# jlink_to_tag.net
KiCad netlist of a schematic drawn in EAGLE
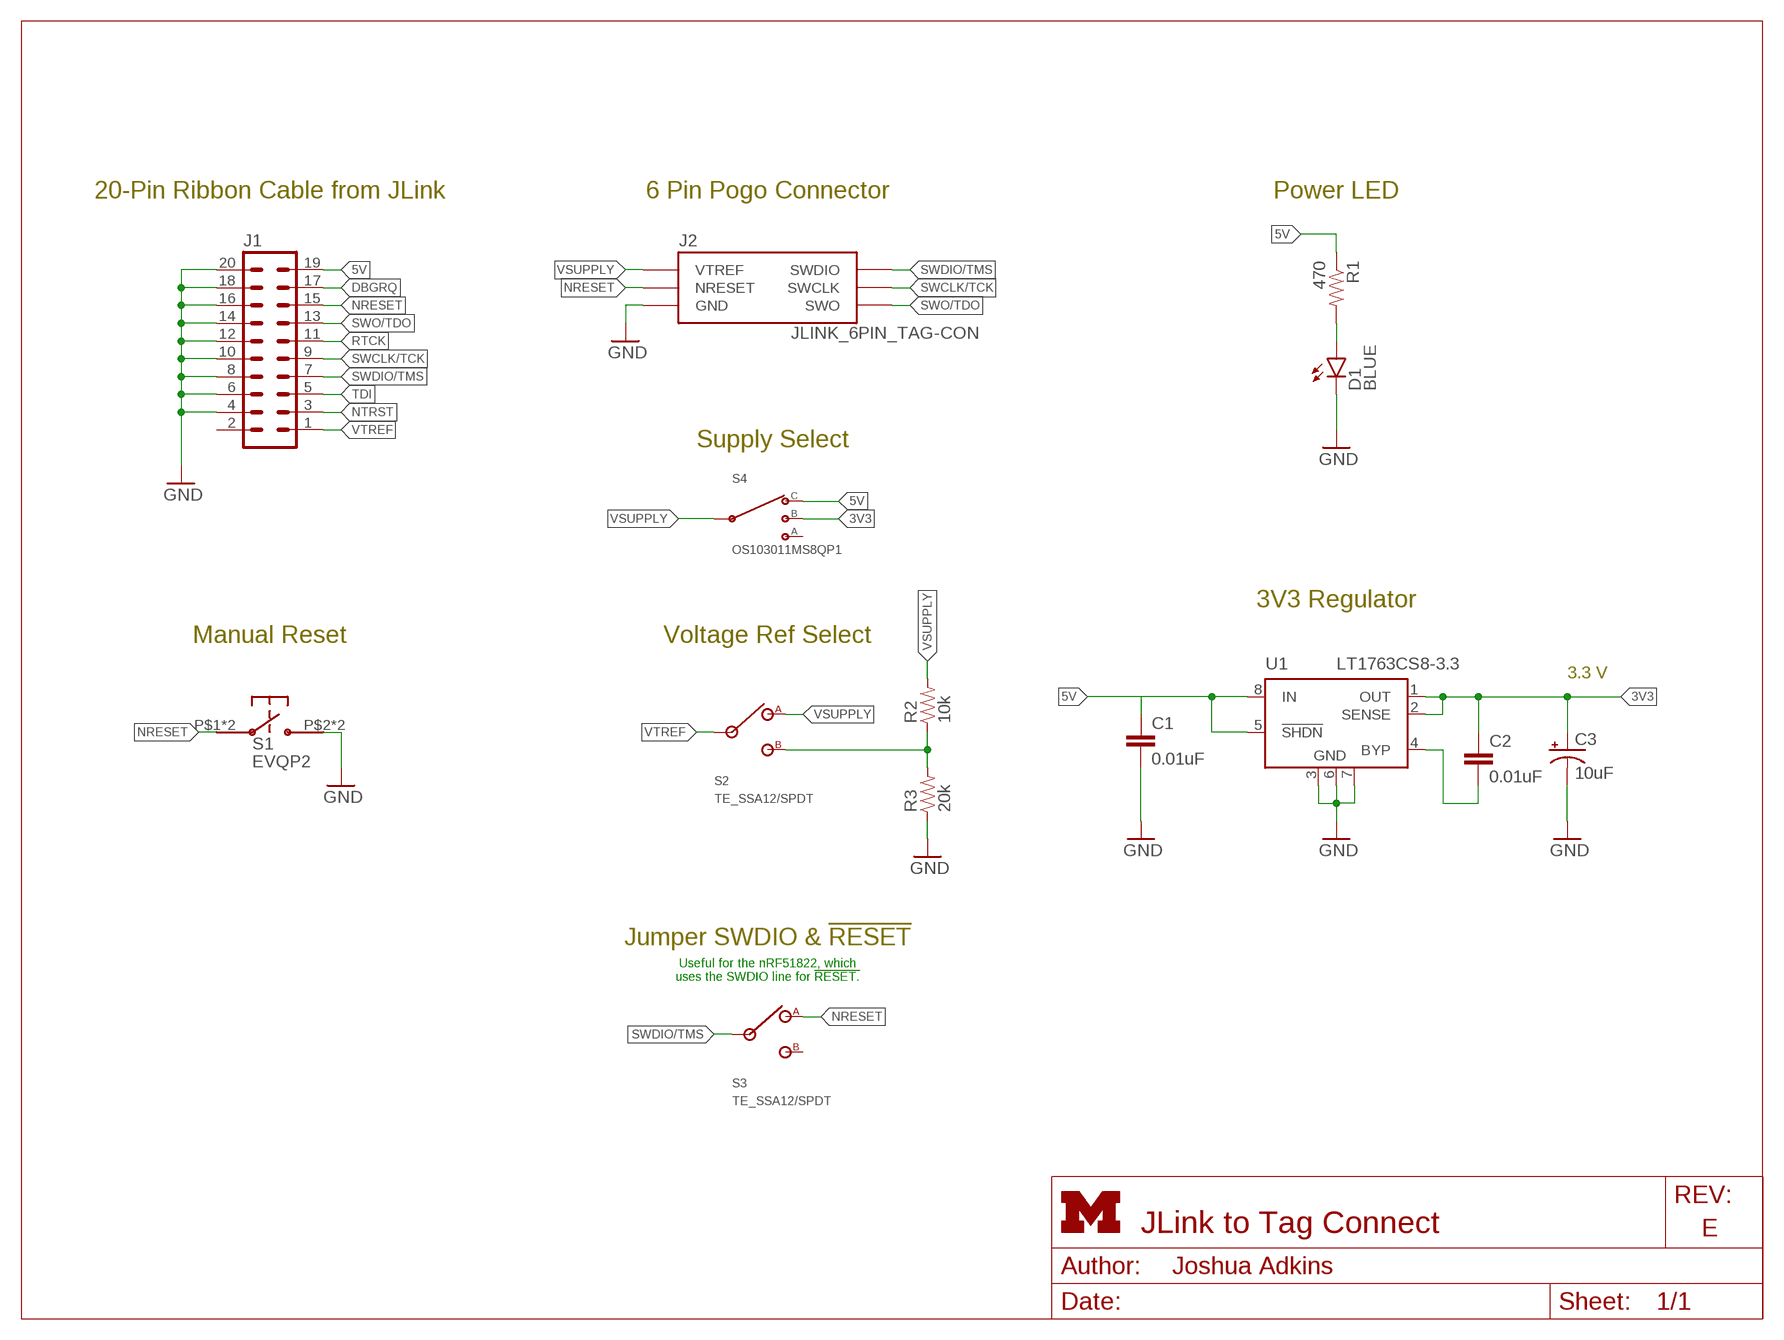
[diagram p0: schematic, sheet 1]

(export (version "E")
  (design (tool "Eeschema 10.0.6"))
  (components
    (comp (ref "C1")
      (value "0.01uF")
      (footprint "eagle-import:C0603")
      (libsource (lib "eagle-import") (part "C-EUC0603"))
    )
    (comp (ref "C2")
      (value "0.01uF")
      (footprint "eagle-import:C0603")
      (libsource (lib "eagle-import") (part "C-EUC0603"))
    )
    (comp (ref "C3")
      (value "10uF")
      (footprint "eagle-import:EIA3216")
      (libsource (lib "eagle-import") (part "CAP_POL1206"))
    )
    (comp (ref "D1")
      (value "BLUE")
      (footprint "eagle-import:LED-0603")
      (libsource (lib "eagle-import") (part "LED-BLUE0603"))
    )
    (comp (ref "J1")
      (value "ML20")
      (footprint "eagle-import:ML20")
      (libsource (lib "eagle-import") (part "ML20"))
    )
    (comp (ref "J2")
      (value "JLINK_6PIN_TAG-CON")
      (footprint "eagle-import:2X3_MALE_SHROUDED_0.100")
      (libsource (lib "eagle-import") (part "JLINK_6PIN_TAG-CON"))
    )
    (comp (ref "R1")
      (value "470")
      (footprint "eagle-import:0603-RES")
      (libsource (lib "eagle-import") (part "RESISTOR0603-RES"))
    )
    (comp (ref "R2")
      (value "10k")
      (footprint "eagle-import:0603-RES")
      (libsource (lib "eagle-import") (part "RESISTOR0603_RES"))
    )
    (comp (ref "R3")
      (value "20k")
      (footprint "eagle-import:0603-RES")
      (libsource (lib "eagle-import") (part "RESISTOR0603_RES"))
    )
    (comp (ref "S1")
      (value "EVQP2")
      (footprint "eagle-import:EVQP2")
      (libsource (lib "eagle-import") (part "EVQP2"))
    )
    (comp (ref "S2")
      (value "TE_SSA12/SPDT")
      (footprint "eagle-import:TE_SSA12_SPDT")
      (fields (field (name "DIGIKEY") "2223-SLW-883935-2A-D-ND") (field (name "MPN") "SLW-883935-2A-D"))
      (libsource (lib "eagle-import") (part "TE_SSA12/SPDT"))
    )
    (comp (ref "S3")
      (value "TE_SSA12/SPDT")
      (footprint "eagle-import:TE_SSA12_SPDT")
      (fields (field (name "DIGIKEY") "2223-SLW-883935-2A-D-ND") (field (name "MPN") "SLW-883935-2A-D"))
      (libsource (lib "eagle-import") (part "TE_SSA12/SPDT"))
    )
    (comp (ref "S4")
      (value "OS103011MS8QP1")
      (footprint "eagle-import:OS102011MS8QP1")
      (libsource (lib "eagle-import") (part "OS103011MS8QP1"))
    )
    (comp (ref "U1")
      (value "LT1763CS8-3.3")
      (footprint "eagle-import:SOIC8")
      (libsource (lib "eagle-import") (part "LT1763CS8-3.3"))
    )
  )
  (nets
    (net (code "1") (name "3V3") (class "Default")
      (node (ref "C2") (pin "1") (pinfunction "1_1") (pintype "passive"))
      (node (ref "C3") (pin "A") (pinfunction "+_A") (pintype "passive"))
      (node (ref "S4") (pin "3") (pinfunction "2_3") (pintype "bidirectional"))
      (node (ref "U1") (pin "1") (pinfunction "OUT_1") (pintype "passive"))
      (node (ref "U1") (pin "2") (pinfunction "SENSE_2") (pintype "input"))
    )
    (net (code "2") (name "5V") (class "Default")
      (node (ref "C1") (pin "1") (pinfunction "1_1") (pintype "passive"))
      (node (ref "J1") (pin "19") (pinfunction "19_19") (pintype "passive"))
      (node (ref "R1") (pin "1") (pinfunction "1_1") (pintype "passive"))
      (node (ref "S4") (pin "4") (pinfunction "3_4") (pintype "bidirectional"))
      (node (ref "U1") (pin "5") (pinfunction "~{SHDN}_5") (pintype "input"))
      (node (ref "U1") (pin "8") (pinfunction "IN_8") (pintype "input"))
    )
    (net (code "3") (name "DBGRQ") (class "Default")
      (node (ref "J1") (pin "17") (pinfunction "17_17") (pintype "passive"))
    )
    (net (code "4") (name "GND") (class "Default")
      (node (ref "C1") (pin "2") (pinfunction "2_2") (pintype "passive"))
      (node (ref "C3") (pin "C") (pinfunction "-_C") (pintype "passive"))
      (node (ref "D1") (pin "C") (pinfunction "C_C") (pintype "passive"))
      (node (ref "J1") (pin "10") (pinfunction "10_10") (pintype "passive"))
      (node (ref "J1") (pin "12") (pinfunction "12_12") (pintype "passive"))
      (node (ref "J1") (pin "14") (pinfunction "14_14") (pintype "passive"))
      (node (ref "J1") (pin "16") (pinfunction "16_16") (pintype "passive"))
      (node (ref "J1") (pin "18") (pinfunction "18_18") (pintype "passive"))
      (node (ref "J1") (pin "20") (pinfunction "20_20") (pintype "passive"))
      (node (ref "J1") (pin "4") (pinfunction "4_4") (pintype "passive"))
      (node (ref "J1") (pin "6") (pinfunction "6_6") (pintype "passive"))
      (node (ref "J1") (pin "8") (pinfunction "8_8") (pintype "passive"))
      (node (ref "J2") (pin "5") (pinfunction "GND_5") (pintype "bidirectional"))
      (node (ref "R3") (pin "1") (pinfunction "1_1") (pintype "passive"))
      (node (ref "S1") (pin "P$2") (pinfunction "P$2_P$2") (pintype "passive"))
      (node (ref "S1") (pin "P$4") (pinfunction "P$2_P$4") (pintype "passive"))
      (node (ref "U1") (pin "3") (pinfunction "GND_3") (pintype "power_in"))
      (node (ref "U1") (pin "6") (pinfunction "GND_6") (pintype "power_in"))
      (node (ref "U1") (pin "7") (pinfunction "GND_7") (pintype "power_in"))
    )
    (net (code "5") (name "NRESET") (class "Default")
      (node (ref "J1") (pin "15") (pinfunction "15_15") (pintype "passive"))
      (node (ref "J2") (pin "3") (pinfunction "NRESET_3") (pintype "bidirectional"))
      (node (ref "S1") (pin "P$1") (pinfunction "P$1_P$1") (pintype "passive"))
      (node (ref "S1") (pin "P$3") (pinfunction "P$1_P$3") (pintype "passive"))
      (node (ref "S3") (pin "1") (pinfunction "A_1") (pintype "bidirectional"))
    )
    (net (code "6") (name "NTRST") (class "Default")
      (node (ref "J1") (pin "3") (pinfunction "3_3") (pintype "passive"))
    )
    (net (code "7") (name "Net-(D1-PadA)") (class "Default")
      (node (ref "D1") (pin "A") (pinfunction "A_A") (pintype "passive"))
      (node (ref "R1") (pin "2") (pinfunction "2_2") (pintype "passive"))
    )
    (net (code "8") (name "Net-(S2-B)") (class "Default")
      (node (ref "R2") (pin "1") (pinfunction "1_1") (pintype "passive"))
      (node (ref "R3") (pin "2") (pinfunction "2_2") (pintype "passive"))
      (node (ref "S2") (pin "2") (pinfunction "B_2") (pintype "bidirectional"))
    )
    (net (code "9") (name "Net-(U1-BYP)") (class "Default")
      (node (ref "C2") (pin "2") (pinfunction "2_2") (pintype "passive"))
      (node (ref "U1") (pin "4") (pinfunction "BYP_4") (pintype "input"))
    )
    (net (code "10") (name "RTCK") (class "Default")
      (node (ref "J1") (pin "11") (pinfunction "11_11") (pintype "passive"))
    )
    (net (code "11") (name "SWCLK{slash}TCK") (class "Default")
      (node (ref "J1") (pin "9") (pinfunction "9_9") (pintype "passive"))
      (node (ref "J2") (pin "4") (pinfunction "SWCLK_4") (pintype "bidirectional"))
    )
    (net (code "12") (name "SWDIO{slash}TMS") (class "Default")
      (node (ref "J1") (pin "7") (pinfunction "7_7") (pintype "passive"))
      (node (ref "J2") (pin "2") (pinfunction "SWDIO_2") (pintype "bidirectional"))
      (node (ref "S3") (pin "IN") (pinfunction "IN_IN") (pintype "bidirectional"))
    )
    (net (code "13") (name "SWO{slash}TDO") (class "Default")
      (node (ref "J1") (pin "13") (pinfunction "13_13") (pintype "passive"))
      (node (ref "J2") (pin "6") (pinfunction "SWO_6") (pintype "bidirectional"))
    )
    (net (code "14") (name "TDI") (class "Default")
      (node (ref "J1") (pin "5") (pinfunction "5_5") (pintype "passive"))
    )
    (net (code "15") (name "VSUPPLY") (class "Default")
      (node (ref "J2") (pin "1") (pinfunction "VTREF_1") (pintype "bidirectional"))
      (node (ref "R2") (pin "2") (pinfunction "2_2") (pintype "passive"))
      (node (ref "S2") (pin "1") (pinfunction "A_1") (pintype "bidirectional"))
      (node (ref "S4") (pin "2") (pinfunction "C_2") (pintype "bidirectional"))
    )
    (net (code "16") (name "VTREF") (class "Default")
      (node (ref "J1") (pin "1") (pinfunction "1_1") (pintype "passive"))
      (node (ref "S2") (pin "IN") (pinfunction "IN_IN") (pintype "bidirectional"))
    )
    (net (code "17") (name "unconnected-(J1-Pad2)") (class "Default")
      (node (ref "J1") (pin "2") (pinfunction "2_2") (pintype "passive"))
    )
    (net (code "18") (name "unconnected-(S3-B-Pad2)") (class "Default")
      (node (ref "S3") (pin "2") (pinfunction "B_2") (pintype "bidirectional"))
    )
    (net (code "19") (name "unconnected-(S4-Pad1)") (class "Default")
      (node (ref "S4") (pin "1") (pinfunction "1_1") (pintype "bidirectional"))
    )
  )
)
